# Layout_Stecksockel.net
KiCad netlist of a schematic drawn in EAGLE
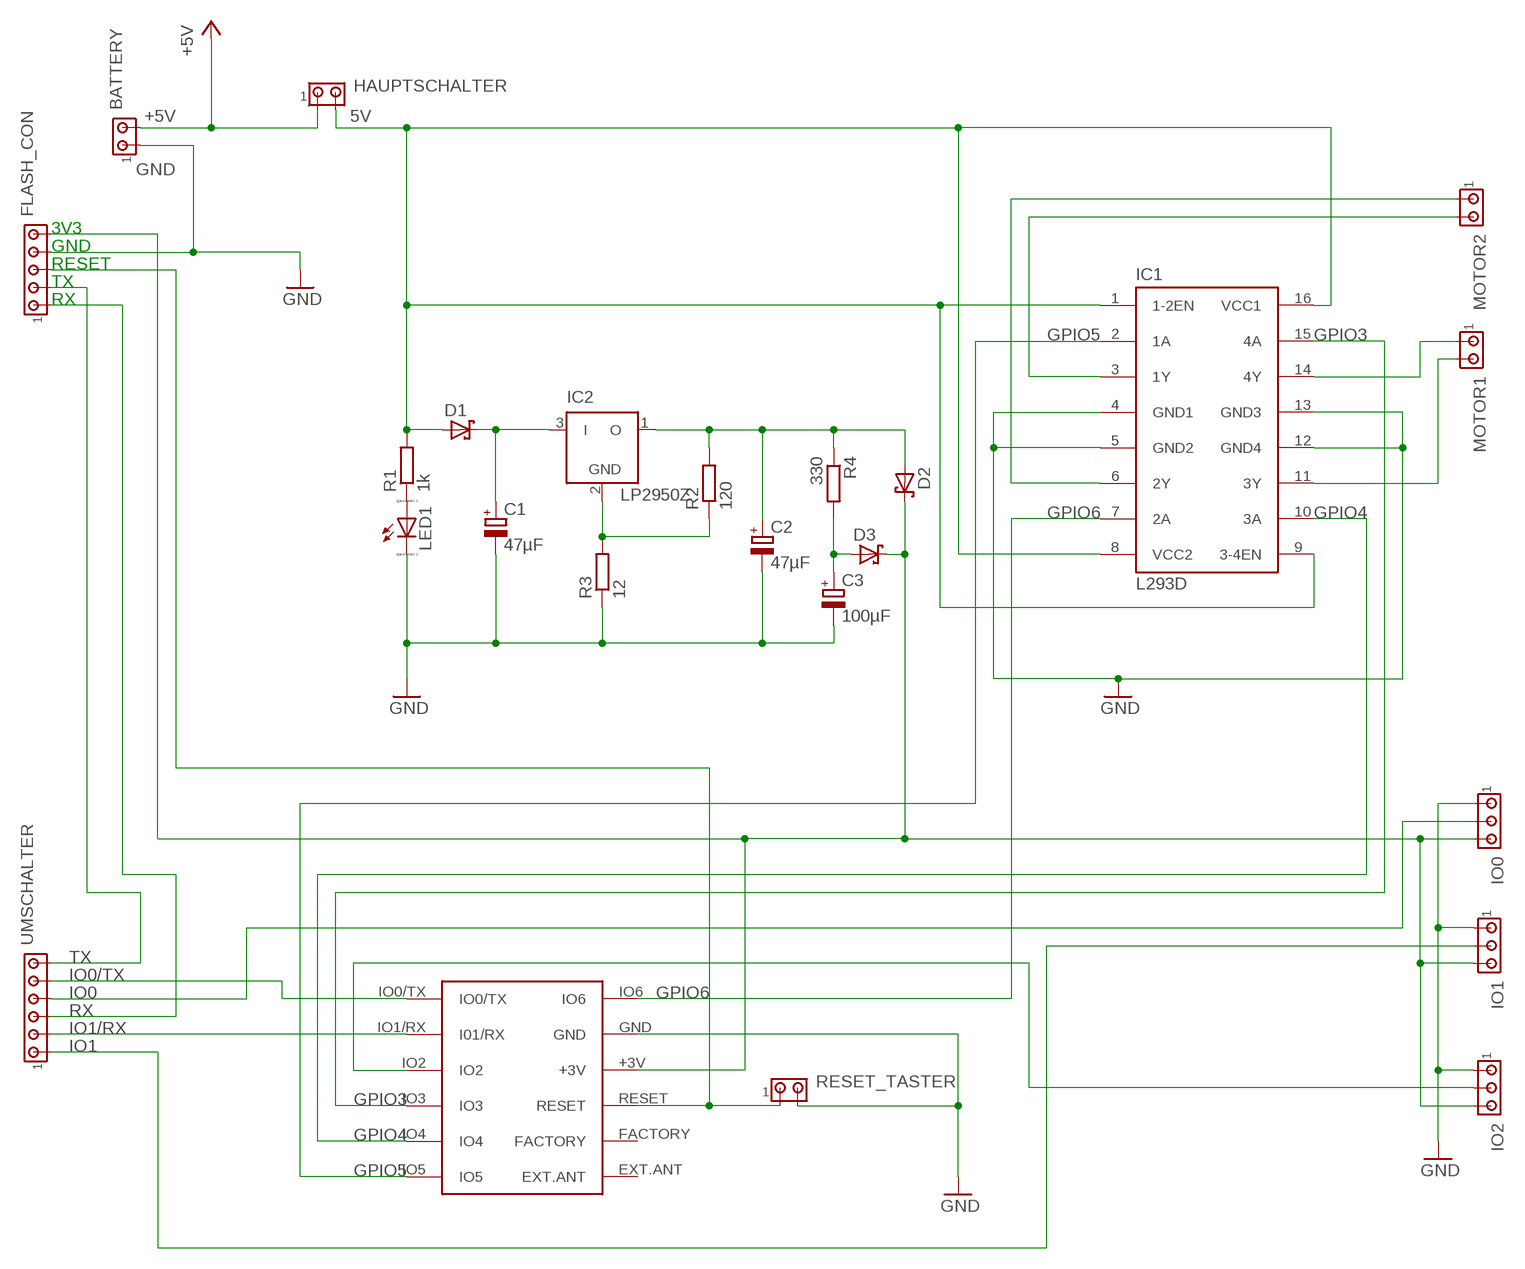
[diagram p0: schematic, sheet 1]

(export (version "E")
  (design (tool "Eeschema 10.0.6"))
  (components
    (comp (ref "BATTERY")
      (value "MTA02-100")
      (footprint "eagle-import:10X02MTA")
      (libsource (lib "eagle-import") (part "MTA02-100"))
    )
    (comp (ref "C1")
      (value "47µF")
      (footprint "eagle-import:E2,5-6E")
      (libsource (lib "eagle-import") (part "CPOL-EUE2,5-6E"))
    )
    (comp (ref "C2")
      (value "47µF")
      (footprint "eagle-import:E2,5-6E")
      (libsource (lib "eagle-import") (part "CPOL-EUE2,5-6E"))
    )
    (comp (ref "C3")
      (value "100µF")
      (footprint "eagle-import:E2,5-6E")
      (libsource (lib "eagle-import") (part "CPOL-EUE2,5-6E"))
    )
    (comp (ref "D1")
      (value "SCHOTTKY-DIODEDO35-7")
      (footprint "eagle-import:DO35-7")
      (libsource (lib "eagle-import") (part "SCHOTTKY-DIODEDO35-7"))
    )
    (comp (ref "D2")
      (value "SCHOTTKY-DIODEDO35-7")
      (footprint "eagle-import:DO35-7")
      (libsource (lib "eagle-import") (part "SCHOTTKY-DIODEDO35-7"))
    )
    (comp (ref "D3")
      (value "SCHOTTKY-DIODEDO35-7")
      (footprint "eagle-import:DO35-7")
      (libsource (lib "eagle-import") (part "SCHOTTKY-DIODEDO35-7"))
    )
    (comp (ref "FLASH_CON")
      (value "MTA05-100")
      (footprint "eagle-import:10X05MTA")
      (libsource (lib "eagle-import") (part "MTA05-100"))
    )
    (comp (ref "HAUPTSCHALTER")
      (value "MTA02-100")
      (footprint "eagle-import:10X02MTA")
      (libsource (lib "eagle-import") (part "MTA02-100"))
    )
    (comp (ref "IC1")
      (value "L293D")
      (footprint "eagle-import:DIL16")
      (libsource (lib "eagle-import") (part "L293D"))
    )
    (comp (ref "IC2")
      (value "LP2950Z")
      (footprint "eagle-import:TO92")
      (libsource (lib "eagle-import") (part "LP2950Z"))
    )
    (comp (ref "IO0")
      (value "MTA03-100")
      (footprint "eagle-import:10X03MTA")
      (libsource (lib "eagle-import") (part "MTA03-100"))
    )
    (comp (ref "IO1")
      (value "MTA03-100")
      (footprint "eagle-import:10X03MTA")
      (libsource (lib "eagle-import") (part "MTA03-100"))
    )
    (comp (ref "IO2")
      (value "MTA03-100")
      (footprint "eagle-import:10X03MTA")
      (libsource (lib "eagle-import") (part "MTA03-100"))
    )
    (comp (ref "LED1")
      (value "LED_ELD260")
      (footprint "eagle-import:LED_LD260")
      (libsource (lib "eagle-import") (part "LED_ELD260"))
    )
    (comp (ref "MOTOR1")
      (value "MTA02-100")
      (footprint "eagle-import:10X02MTA")
      (libsource (lib "eagle-import") (part "MTA02-100"))
    )
    (comp (ref "MOTOR2")
      (value "MTA02-100")
      (footprint "eagle-import:10X02MTA")
      (libsource (lib "eagle-import") (part "MTA02-100"))
    )
    (comp (ref "R1")
      (value "1k")
      (footprint "eagle-import:0207_10")
      (libsource (lib "eagle-import") (part "resistor_R-EU_0207/10"))
    )
    (comp (ref "R2")
      (value "120")
      (footprint "eagle-import:0207_10")
      (libsource (lib "eagle-import") (part "R-EU_0207/10"))
    )
    (comp (ref "R3")
      (value "12")
      (footprint "eagle-import:0207_10")
      (libsource (lib "eagle-import") (part "R-EU_0207/10"))
    )
    (comp (ref "R4")
      (value "330")
      (footprint "eagle-import:0207_10")
      (libsource (lib "eagle-import") (part "R-EU_0207/10"))
    )
    (comp (ref "RESET_TASTER")
      (value "MTA02-100")
      (footprint "eagle-import:10X02MTA")
      (libsource (lib "eagle-import") (part "MTA02-100"))
    )
    (comp (ref "U$1")
      (value "RFDUINO")
      (footprint "eagle-import:RFDUINO")
      (libsource (lib "eagle-import") (part "RFDUINO"))
    )
    (comp (ref "UMSCHALTER")
      (value "MTA06-100")
      (footprint "eagle-import:10X06MTA")
      (libsource (lib "eagle-import") (part "MTA06-100"))
    )
  )
  (nets
    (net (code "1") (name "+5V") (class "Default")
      (node (ref "BATTERY") (pin "2") (pinfunction "2_2") (pintype "passive"))
      (node (ref "HAUPTSCHALTER") (pin "1") (pinfunction "1_1") (pintype "passive"))
    )
    (net (code "2") (name "/5V") (class "Default")
      (node (ref "D1") (pin "A") (pinfunction "A_A") (pintype "passive"))
      (node (ref "HAUPTSCHALTER") (pin "2") (pinfunction "2_2") (pintype "passive"))
      (node (ref "IC1") (pin "1") (pinfunction "1-2EN_1") (pintype "input"))
      (node (ref "IC1") (pin "16") (pinfunction "VCC1_16") (pintype "power_in"))
      (node (ref "IC1") (pin "8") (pinfunction "VCC2_8") (pintype "power_in"))
      (node (ref "IC1") (pin "9") (pinfunction "3-4EN_9") (pintype "input"))
      (node (ref "R1") (pin "2") (pinfunction "2_2") (pintype "passive"))
    )
    (net (code "3") (name "/GPIO3") (class "Default")
      (node (ref "IC1") (pin "15") (pinfunction "4A_15") (pintype "input"))
      (node (ref "U$1") (pin "IO3") (pinfunction "IO3_IO3") (pintype "bidirectional"))
    )
    (net (code "4") (name "/GPIO4") (class "Default")
      (node (ref "IC1") (pin "10") (pinfunction "3A_10") (pintype "input"))
      (node (ref "U$1") (pin "IO4") (pinfunction "IO4_IO4") (pintype "bidirectional"))
    )
    (net (code "5") (name "/GPIO5") (class "Default")
      (node (ref "IC1") (pin "2") (pinfunction "1A_2") (pintype "input"))
      (node (ref "U$1") (pin "IO5") (pinfunction "IO5_IO5") (pintype "bidirectional"))
    )
    (net (code "6") (name "/GPIO6") (class "Default")
      (node (ref "IC1") (pin "7") (pinfunction "2A_7") (pintype "input"))
      (node (ref "U$1") (pin "IO6") (pinfunction "IO6_IO6") (pintype "bidirectional"))
    )
    (net (code "7") (name "/IO0") (class "Default")
      (node (ref "IO0") (pin "2") (pinfunction "2_2") (pintype "passive"))
      (node (ref "UMSCHALTER") (pin "4") (pinfunction "4_4") (pintype "passive"))
    )
    (net (code "8") (name "/IO0{slash}TX") (class "Default")
      (node (ref "U$1") (pin "IO0/TX") (pinfunction "IO0/TX_IO0/TX") (pintype "bidirectional"))
      (node (ref "UMSCHALTER") (pin "5") (pinfunction "5_5") (pintype "passive"))
    )
    (net (code "9") (name "/IO1") (class "Default")
      (node (ref "IO1") (pin "2") (pinfunction "2_2") (pintype "passive"))
      (node (ref "UMSCHALTER") (pin "1") (pinfunction "1_1") (pintype "passive"))
    )
    (net (code "10") (name "/IO1{slash}RX") (class "Default")
      (node (ref "U$1") (pin "IO1/RX") (pinfunction "I01/RX_IO1/RX") (pintype "bidirectional"))
      (node (ref "UMSCHALTER") (pin "2") (pinfunction "2_2") (pintype "passive"))
    )
    (net (code "11") (name "/RX") (class "Default")
      (node (ref "FLASH_CON") (pin "1") (pinfunction "1_1") (pintype "passive"))
      (node (ref "UMSCHALTER") (pin "3") (pinfunction "3_3") (pintype "passive"))
    )
    (net (code "12") (name "/TX") (class "Default")
      (node (ref "FLASH_CON") (pin "2") (pinfunction "2_2") (pintype "passive"))
      (node (ref "UMSCHALTER") (pin "6") (pinfunction "6_6") (pintype "passive"))
    )
    (net (code "13") (name "GND") (class "Default")
      (node (ref "BATTERY") (pin "1") (pinfunction "1_1") (pintype "passive"))
      (node (ref "C1") (pin "-") (pinfunction "-_-") (pintype "passive"))
      (node (ref "C2") (pin "-") (pinfunction "-_-") (pintype "passive"))
      (node (ref "C3") (pin "-") (pinfunction "-_-") (pintype "passive"))
      (node (ref "FLASH_CON") (pin "4") (pinfunction "4_4") (pintype "passive"))
      (node (ref "IC1") (pin "12") (pinfunction "GND4_12") (pintype "power_in"))
      (node (ref "IC1") (pin "13") (pinfunction "GND3_13") (pintype "power_in"))
      (node (ref "IC1") (pin "4") (pinfunction "GND1_4") (pintype "power_in"))
      (node (ref "IC1") (pin "5") (pinfunction "GND2_5") (pintype "power_in"))
      (node (ref "IO0") (pin "1") (pinfunction "1_1") (pintype "passive"))
      (node (ref "IO1") (pin "1") (pinfunction "1_1") (pintype "passive"))
      (node (ref "IO2") (pin "1") (pinfunction "1_1") (pintype "passive"))
      (node (ref "LED1") (pin "K") (pinfunction "C_K") (pintype "passive"))
      (node (ref "R3") (pin "1") (pinfunction "1_1") (pintype "passive"))
      (node (ref "RESET_TASTER") (pin "2") (pinfunction "2_2") (pintype "passive"))
      (node (ref "U$1") (pin "GND") (pinfunction "GND_GND") (pintype "power_in"))
    )
    (net (code "14") (name "Net-(C3-Pad+)") (class "Default")
      (node (ref "C3") (pin "+") (pinfunction "+_+") (pintype "passive"))
      (node (ref "D3") (pin "A") (pinfunction "A_A") (pintype "passive"))
      (node (ref "R4") (pin "2") (pinfunction "2_2") (pintype "passive"))
    )
    (net (code "15") (name "Net-(D2-PadC)") (class "Default")
      (node (ref "D2") (pin "C") (pinfunction "C_C") (pintype "passive"))
      (node (ref "D3") (pin "C") (pinfunction "C_C") (pintype "passive"))
      (node (ref "FLASH_CON") (pin "5") (pinfunction "5_5") (pintype "passive"))
      (node (ref "IO0") (pin "3") (pinfunction "3_3") (pintype "passive"))
      (node (ref "IO1") (pin "3") (pinfunction "3_3") (pintype "passive"))
      (node (ref "IO2") (pin "3") (pinfunction "3_3") (pintype "passive"))
      (node (ref "U$1") (pin "+3V") (pinfunction "+3V_+3V") (pintype "power_in"))
    )
    (net (code "16") (name "Net-(FLASH_CON-Pad3)") (class "Default")
      (node (ref "FLASH_CON") (pin "3") (pinfunction "3_3") (pintype "passive"))
      (node (ref "RESET_TASTER") (pin "1") (pinfunction "1_1") (pintype "passive"))
      (node (ref "U$1") (pin "RESET") (pinfunction "RESET_RESET") (pintype "input"))
    )
    (net (code "17") (name "Net-(IC1-1Y)") (class "Default")
      (node (ref "IC1") (pin "3") (pinfunction "1Y_3") (pintype "output"))
      (node (ref "MOTOR2") (pin "2") (pinfunction "2_2") (pintype "passive"))
    )
    (net (code "18") (name "Net-(IC1-2Y)") (class "Default")
      (node (ref "IC1") (pin "6") (pinfunction "2Y_6") (pintype "output"))
      (node (ref "MOTOR2") (pin "1") (pinfunction "1_1") (pintype "passive"))
    )
    (net (code "19") (name "Net-(IC1-3Y)") (class "Default")
      (node (ref "IC1") (pin "11") (pinfunction "3Y_11") (pintype "output"))
      (node (ref "MOTOR1") (pin "2") (pinfunction "2_2") (pintype "passive"))
    )
    (net (code "20") (name "Net-(IC1-4Y)") (class "Default")
      (node (ref "IC1") (pin "14") (pinfunction "4Y_14") (pintype "output"))
      (node (ref "MOTOR1") (pin "1") (pinfunction "1_1") (pintype "passive"))
    )
    (net (code "21") (name "Net-(IC2-GND)") (class "Default")
      (node (ref "IC2") (pin "2") (pinfunction "GND_2") (pintype "power_in"))
      (node (ref "R2") (pin "1") (pinfunction "1_1") (pintype "passive"))
      (node (ref "R3") (pin "2") (pinfunction "2_2") (pintype "passive"))
    )
    (net (code "22") (name "Net-(IC2-I)") (class "Default")
      (node (ref "C1") (pin "+") (pinfunction "+_+") (pintype "passive"))
      (node (ref "D1") (pin "C") (pinfunction "C_C") (pintype "passive"))
      (node (ref "IC2") (pin "3") (pinfunction "I_3") (pintype "input"))
    )
    (net (code "23") (name "Net-(IC2-O)") (class "Default")
      (node (ref "C2") (pin "+") (pinfunction "+_+") (pintype "passive"))
      (node (ref "D2") (pin "A") (pinfunction "A_A") (pintype "passive"))
      (node (ref "IC2") (pin "1") (pinfunction "O_1") (pintype "input"))
      (node (ref "R2") (pin "2") (pinfunction "2_2") (pintype "passive"))
      (node (ref "R4") (pin "1") (pinfunction "1_1") (pintype "passive"))
    )
    (net (code "24") (name "Net-(IO2-Pad2)") (class "Default")
      (node (ref "IO2") (pin "2") (pinfunction "2_2") (pintype "passive"))
      (node (ref "U$1") (pin "IO2") (pinfunction "IO2_IO2") (pintype "bidirectional"))
    )
    (net (code "25") (name "Net-(LED1-PadA)") (class "Default")
      (node (ref "LED1") (pin "A") (pinfunction "A_A") (pintype "passive"))
      (node (ref "R1") (pin "1") (pinfunction "1_1") (pintype "passive"))
    )
    (net (code "26") (name "unconnected-(U$1-PadEXT.ANT)") (class "Default")
      (node (ref "U$1") (pin "EXT.ANT") (pinfunction "EXT.ANT_EXT.ANT") (pintype "input"))
    )
    (net (code "27") (name "unconnected-(U$1-PadFACTORY)") (class "Default")
      (node (ref "U$1") (pin "FACTORY") (pinfunction "FACTORY_FACTORY") (pintype "input"))
    )
  )
)
